# Schematic.net
KiCad netlist of a schematic drawn in Altium Designer
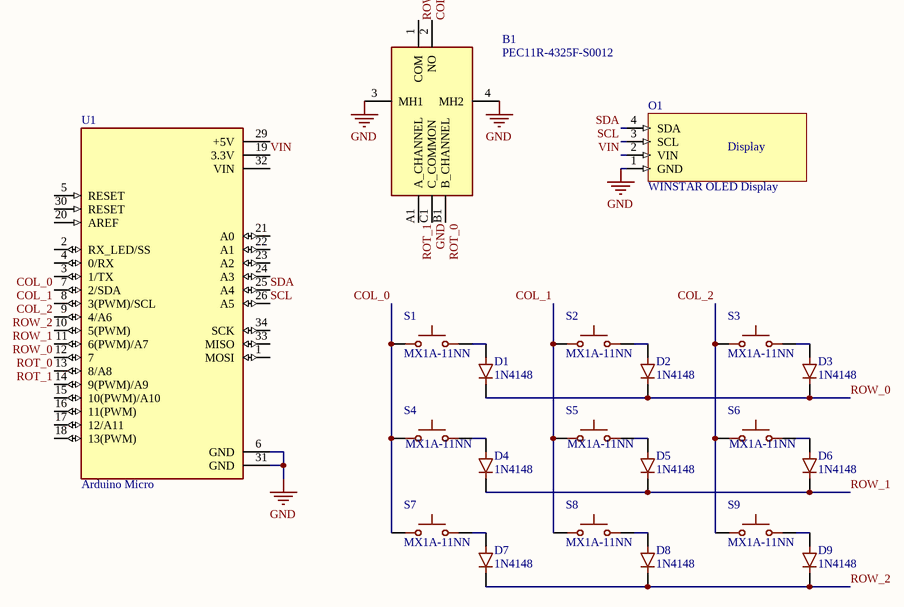
[diagram p0: Schematic.SchDoc]

(export (version "E")
  (design (tool "Eeschema 10.0.6"))
  (components
    (comp (ref "B1")
      (value "PEC11R-4325F-S0012")
      (footprint "PEC11R-4315F-S0012")
      (description "Rotary Encoder Mechanical 12 Quadrature (Incremental) Vertical")
      (fields (field (name "MOUSER PART NUMBER") "652-PEC11R4325FS0012"))
      (libsource (lib "Schematic_Lib") (part "PEC11R-4315F-S0012"))
    )
    (comp (ref "D1")
      (value "1N4148")
      (footprint "1N4148 Diode")
      (description "Diode Standard 75V 200mA Surface Mount SOD-523F")
      (fields (field (name "MF") "ON Semiconductor"))
      (libsource (lib "Schematic_Lib") (part "1N4148"))
    )
    (comp (ref "D2")
      (value "1N4148")
      (footprint "1N4148 Diode")
      (description "Diode Standard 75V 200mA Surface Mount SOD-523F")
      (fields (field (name "MF") "ON Semiconductor"))
      (libsource (lib "Schematic_Lib") (part "1N4148"))
    )
    (comp (ref "D3")
      (value "1N4148")
      (footprint "1N4148 Diode")
      (description "Diode Standard 75V 200mA Surface Mount SOD-523F")
      (fields (field (name "MF") "ON Semiconductor"))
      (libsource (lib "Schematic_Lib") (part "1N4148"))
    )
    (comp (ref "D4")
      (value "1N4148")
      (footprint "1N4148 Diode")
      (description "Diode Standard 75V 200mA Surface Mount SOD-523F")
      (fields (field (name "MF") "ON Semiconductor"))
      (libsource (lib "Schematic_Lib") (part "1N4148"))
    )
    (comp (ref "D5")
      (value "1N4148")
      (footprint "1N4148 Diode")
      (description "Diode Standard 75V 200mA Surface Mount SOD-523F")
      (fields (field (name "MF") "ON Semiconductor"))
      (libsource (lib "Schematic_Lib") (part "1N4148"))
    )
    (comp (ref "D6")
      (value "1N4148")
      (footprint "1N4148 Diode")
      (description "Diode Standard 75V 200mA Surface Mount SOD-523F")
      (fields (field (name "MF") "ON Semiconductor"))
      (libsource (lib "Schematic_Lib") (part "1N4148"))
    )
    (comp (ref "D7")
      (value "1N4148")
      (footprint "1N4148 Diode")
      (description "Diode Standard 75V 200mA Surface Mount SOD-523F")
      (fields (field (name "MF") "ON Semiconductor"))
      (libsource (lib "Schematic_Lib") (part "1N4148"))
    )
    (comp (ref "D8")
      (value "1N4148")
      (footprint "1N4148 Diode")
      (description "Diode Standard 75V 200mA Surface Mount SOD-523F")
      (fields (field (name "MF") "ON Semiconductor"))
      (libsource (lib "Schematic_Lib") (part "1N4148"))
    )
    (comp (ref "D9")
      (value "1N4148")
      (footprint "1N4148 Diode")
      (description "Diode Standard 75V 200mA Surface Mount SOD-523F")
      (fields (field (name "MF") "ON Semiconductor"))
      (libsource (lib "Schematic_Lib") (part "1N4148"))
    )
    (comp (ref "O1")
      (value "WINSTAR OLED Display")
      (footprint "WINSTAR OLED Display")
      (description "WEA012832FWPP3N00000")
      (libsource (lib "Schematic_Lib") (part "WINSTAR OLED Display"))
    )
    (comp (ref "S1")
      (value "MX1A-11NN")
      (footprint "SW_MX1A-11NN")
      (fields (field (name "MF") "Cherry"))
      (libsource (lib "Schematic_Lib") (part "MX1A-11NN"))
    )
    (comp (ref "S2")
      (value "MX1A-11NN")
      (footprint "SW_MX1A-11NN")
      (fields (field (name "MF") "Cherry"))
      (libsource (lib "Schematic_Lib") (part "MX1A-11NN"))
    )
    (comp (ref "S3")
      (value "MX1A-11NN")
      (footprint "SW_MX1A-11NN")
      (fields (field (name "MF") "Cherry"))
      (libsource (lib "Schematic_Lib") (part "MX1A-11NN"))
    )
    (comp (ref "S4")
      (value "MX1A-11NN")
      (footprint "SW_MX1A-11NN")
      (fields (field (name "MF") "Cherry"))
      (libsource (lib "Schematic_Lib") (part "MX1A-11NN"))
    )
    (comp (ref "S5")
      (value "MX1A-11NN")
      (footprint "SW_MX1A-11NN")
      (fields (field (name "MF") "Cherry"))
      (libsource (lib "Schematic_Lib") (part "MX1A-11NN"))
    )
    (comp (ref "S6")
      (value "MX1A-11NN")
      (footprint "SW_MX1A-11NN")
      (fields (field (name "MF") "Cherry"))
      (libsource (lib "Schematic_Lib") (part "MX1A-11NN"))
    )
    (comp (ref "S7")
      (value "MX1A-11NN")
      (footprint "SW_MX1A-11NN")
      (fields (field (name "MF") "Cherry"))
      (libsource (lib "Schematic_Lib") (part "MX1A-11NN"))
    )
    (comp (ref "S8")
      (value "MX1A-11NN")
      (footprint "SW_MX1A-11NN")
      (fields (field (name "MF") "Cherry"))
      (libsource (lib "Schematic_Lib") (part "MX1A-11NN"))
    )
    (comp (ref "S9")
      (value "MX1A-11NN")
      (footprint "SW_MX1A-11NN")
      (fields (field (name "MF") "Cherry"))
      (libsource (lib "Schematic_Lib") (part "MX1A-11NN"))
    )
    (comp (ref "U1")
      (value "Arduino Micro")
      (footprint "Arduino Micro")
      (description "Microcontroller board based on the ATmega32u4")
      (fields (field (name "MF") "Arduino"))
      (libsource (lib "Schlib1") (part "Arduino Micro"))
    )
  )
  (nets
    (net (code "1") (name "/COL_0") (class "Default")
      (node (ref "B1") (pin "2") (pinfunction "NO_2") (pintype "passive"))
      (node (ref "S1") (pin "1") (pinfunction "1_1") (pintype "passive"))
      (node (ref "S4") (pin "1") (pinfunction "1_1") (pintype "passive"))
      (node (ref "S7") (pin "1") (pinfunction "1_1") (pintype "passive"))
      (node (ref "U1") (pin "7") (pinfunction "2/SDA_7") (pintype "bidirectional"))
    )
    (net (code "2") (name "/COL_1") (class "Default")
      (node (ref "S2") (pin "1") (pinfunction "1_1") (pintype "passive"))
      (node (ref "S5") (pin "1") (pinfunction "1_1") (pintype "passive"))
      (node (ref "S8") (pin "1") (pinfunction "1_1") (pintype "passive"))
      (node (ref "U1") (pin "8") (pinfunction "3(PWM)/SCL_8") (pintype "bidirectional"))
    )
    (net (code "3") (name "/COL_2") (class "Default")
      (node (ref "S3") (pin "1") (pinfunction "1_1") (pintype "passive"))
      (node (ref "S6") (pin "1") (pinfunction "1_1") (pintype "passive"))
      (node (ref "S9") (pin "1") (pinfunction "1_1") (pintype "passive"))
      (node (ref "U1") (pin "9") (pinfunction "4/A6_9") (pintype "bidirectional"))
    )
    (net (code "4") (name "/ROT_0") (class "Default")
      (node (ref "B1") (pin "B1") (pinfunction "B_CHANNEL_B1") (pintype "passive"))
      (node (ref "U1") (pin "13") (pinfunction "8/A8_13") (pintype "bidirectional"))
    )
    (net (code "5") (name "/ROT_1") (class "Default")
      (node (ref "B1") (pin "A1") (pinfunction "A_CHANNEL_A1") (pintype "passive"))
      (node (ref "U1") (pin "14") (pinfunction "9(PWM)/A9_14") (pintype "bidirectional"))
    )
    (net (code "6") (name "/ROW_0") (class "Default")
      (node (ref "B1") (pin "1") (pinfunction "COM_1") (pintype "passive"))
      (node (ref "D1") (pin "K") (pinfunction "K_K") (pintype "passive"))
      (node (ref "D2") (pin "K") (pinfunction "K_K") (pintype "passive"))
      (node (ref "D3") (pin "K") (pinfunction "K_K") (pintype "passive"))
      (node (ref "U1") (pin "12") (pinfunction "7_12") (pintype "bidirectional"))
    )
    (net (code "7") (name "/ROW_1") (class "Default")
      (node (ref "D4") (pin "K") (pinfunction "K_K") (pintype "passive"))
      (node (ref "D5") (pin "K") (pinfunction "K_K") (pintype "passive"))
      (node (ref "D6") (pin "K") (pinfunction "K_K") (pintype "passive"))
      (node (ref "U1") (pin "11") (pinfunction "6(PWM)/A7_11") (pintype "bidirectional"))
    )
    (net (code "8") (name "/ROW_2") (class "Default")
      (node (ref "D7") (pin "K") (pinfunction "K_K") (pintype "passive"))
      (node (ref "D8") (pin "K") (pinfunction "K_K") (pintype "passive"))
      (node (ref "D9") (pin "K") (pinfunction "K_K") (pintype "passive"))
      (node (ref "U1") (pin "10") (pinfunction "5(PWM)_10") (pintype "bidirectional"))
    )
    (net (code "9") (name "/SCL") (class "Default")
      (node (ref "O1") (pin "3") (pinfunction "SCL_3") (pintype "input"))
      (node (ref "U1") (pin "26") (pinfunction "A5_26") (pintype "bidirectional"))
    )
    (net (code "10") (name "/SDA") (class "Default")
      (node (ref "O1") (pin "4") (pinfunction "SDA_4") (pintype "input"))
      (node (ref "U1") (pin "25") (pinfunction "A4_25") (pintype "bidirectional"))
    )
    (net (code "11") (name "/VIN") (class "Default")
      (node (ref "O1") (pin "2") (pinfunction "VIN_2") (pintype "input"))
      (node (ref "U1") (pin "19") (pinfunction "3.3V_19") (pintype "power_in"))
    )
    (net (code "12") (name "GND") (class "Default")
      (node (ref "B1") (pin "3") (pinfunction "MH1_3") (pintype "passive"))
      (node (ref "B1") (pin "4") (pinfunction "MH2_4") (pintype "passive"))
      (node (ref "B1") (pin "C1") (pinfunction "C_COMMON_C1") (pintype "passive"))
      (node (ref "O1") (pin "1") (pinfunction "GND_1") (pintype "input"))
      (node (ref "U1") (pin "31") (pinfunction "GND_31") (pintype "power_in"))
      (node (ref "U1") (pin "6") (pinfunction "GND_6") (pintype "power_in"))
    )
    (net (code "13") (name "Net-(D1-PadA)") (class "Default")
      (node (ref "D1") (pin "A") (pinfunction "A_A") (pintype "passive"))
      (node (ref "S1") (pin "2") (pinfunction "2_2") (pintype "passive"))
    )
    (net (code "14") (name "Net-(D2-PadA)") (class "Default")
      (node (ref "D2") (pin "A") (pinfunction "A_A") (pintype "passive"))
      (node (ref "S2") (pin "2") (pinfunction "2_2") (pintype "passive"))
    )
    (net (code "15") (name "Net-(D3-PadA)") (class "Default")
      (node (ref "D3") (pin "A") (pinfunction "A_A") (pintype "passive"))
      (node (ref "S3") (pin "2") (pinfunction "2_2") (pintype "passive"))
    )
    (net (code "16") (name "Net-(D4-PadA)") (class "Default")
      (node (ref "D4") (pin "A") (pinfunction "A_A") (pintype "passive"))
      (node (ref "S4") (pin "2") (pinfunction "2_2") (pintype "passive"))
    )
    (net (code "17") (name "Net-(D5-PadA)") (class "Default")
      (node (ref "D5") (pin "A") (pinfunction "A_A") (pintype "passive"))
      (node (ref "S5") (pin "2") (pinfunction "2_2") (pintype "passive"))
    )
    (net (code "18") (name "Net-(D6-PadA)") (class "Default")
      (node (ref "D6") (pin "A") (pinfunction "A_A") (pintype "passive"))
      (node (ref "S6") (pin "2") (pinfunction "2_2") (pintype "passive"))
    )
    (net (code "19") (name "Net-(D7-PadA)") (class "Default")
      (node (ref "D7") (pin "A") (pinfunction "A_A") (pintype "passive"))
      (node (ref "S7") (pin "2") (pinfunction "2_2") (pintype "passive"))
    )
    (net (code "20") (name "Net-(D8-PadA)") (class "Default")
      (node (ref "D8") (pin "A") (pinfunction "A_A") (pintype "passive"))
      (node (ref "S8") (pin "2") (pinfunction "2_2") (pintype "passive"))
    )
    (net (code "21") (name "Net-(D9-PadA)") (class "Default")
      (node (ref "D9") (pin "A") (pinfunction "A_A") (pintype "passive"))
      (node (ref "S9") (pin "2") (pinfunction "2_2") (pintype "passive"))
    )
    (net (code "22") (name "unconnected-(U1-+5V-Pad29)") (class "Default")
      (node (ref "U1") (pin "29") (pinfunction "+5V_29") (pintype "power_in"))
    )
    (net (code "23") (name "unconnected-(U1-0{slash}RX-Pad4)") (class "Default")
      (node (ref "U1") (pin "4") (pinfunction "0/RX_4") (pintype "bidirectional"))
    )
    (net (code "24") (name "unconnected-(U1-1{slash}TX-Pad3)") (class "Default")
      (node (ref "U1") (pin "3") (pinfunction "1/TX_3") (pintype "bidirectional"))
    )
    (net (code "25") (name "unconnected-(U1-10(PWM){slash}A10-Pad15)") (class "Default")
      (node (ref "U1") (pin "15") (pinfunction "10(PWM)/A10_15") (pintype "bidirectional"))
    )
    (net (code "26") (name "unconnected-(U1-11(PWM)-Pad16)") (class "Default")
      (node (ref "U1") (pin "16") (pinfunction "11(PWM)_16") (pintype "bidirectional"))
    )
    (net (code "27") (name "unconnected-(U1-12{slash}A11-Pad17)") (class "Default")
      (node (ref "U1") (pin "17") (pinfunction "12/A11_17") (pintype "bidirectional"))
    )
    (net (code "28") (name "unconnected-(U1-13(PWM)-Pad18)") (class "Default")
      (node (ref "U1") (pin "18") (pinfunction "13(PWM)_18") (pintype "bidirectional"))
    )
    (net (code "29") (name "unconnected-(U1-A0-Pad21)") (class "Default")
      (node (ref "U1") (pin "21") (pinfunction "A0_21") (pintype "bidirectional"))
    )
    (net (code "30") (name "unconnected-(U1-A1-Pad22)") (class "Default")
      (node (ref "U1") (pin "22") (pinfunction "A1_22") (pintype "bidirectional"))
    )
    (net (code "31") (name "unconnected-(U1-A2-Pad23)") (class "Default")
      (node (ref "U1") (pin "23") (pinfunction "A2_23") (pintype "bidirectional"))
    )
    (net (code "32") (name "unconnected-(U1-A3-Pad24)") (class "Default")
      (node (ref "U1") (pin "24") (pinfunction "A3_24") (pintype "bidirectional"))
    )
    (net (code "33") (name "unconnected-(U1-AREF-Pad20)") (class "Default")
      (node (ref "U1") (pin "20") (pinfunction "AREF_20") (pintype "input"))
    )
    (net (code "34") (name "unconnected-(U1-MISO-Pad33)") (class "Default")
      (node (ref "U1") (pin "33") (pinfunction "MISO_33") (pintype "bidirectional"))
    )
    (net (code "35") (name "unconnected-(U1-MOSI-Pad1)") (class "Default")
      (node (ref "U1") (pin "1") (pinfunction "MOSI_1") (pintype "bidirectional"))
    )
    (net (code "36") (name "unconnected-(U1-RESET-Pad5)") (class "Default")
      (node (ref "U1") (pin "5") (pinfunction "RESET_5") (pintype "input"))
    )
    (net (code "37") (name "unconnected-(U1-RESET-Pad30)") (class "Default")
      (node (ref "U1") (pin "30") (pinfunction "RESET_30") (pintype "input"))
    )
    (net (code "38") (name "unconnected-(U1-RX_LED{slash}SS-Pad2)") (class "Default")
      (node (ref "U1") (pin "2") (pinfunction "RX_LED/SS_2") (pintype "bidirectional"))
    )
    (net (code "39") (name "unconnected-(U1-SCK-Pad34)") (class "Default")
      (node (ref "U1") (pin "34") (pinfunction "SCK_34") (pintype "bidirectional"))
    )
    (net (code "40") (name "unconnected-(U1-VIN-Pad32)") (class "Default")
      (node (ref "U1") (pin "32") (pinfunction "VIN_32") (pintype "power_in"))
    )
  )
)
